# SimCard.net
KiCad netlist of a schematic drawn in Altium Designer
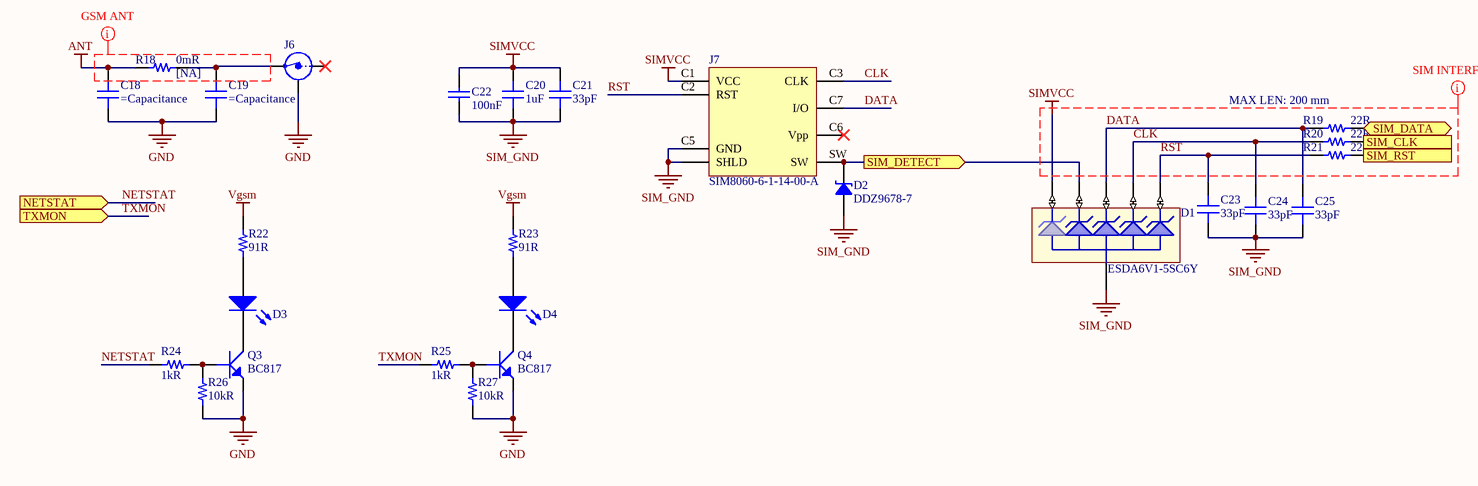
[diagram p0: SimCard.SchDoc]

(export (version "E")
  (design (tool "Eeschema 10.0.6"))
  (components
    (comp (ref "C18")
      (value "~")
      (footprint "CAP 0603/1608")
      (description "Ceramic, SMT Capacitor")
      (libsource (lib "yildizIoT Library") (part "Capacitor - Ceramic"))
    )
    (comp (ref "C19")
      (value "~")
      (footprint "CAP 0603/1608")
      (description "Ceramic, SMT Capacitor")
      (libsource (lib "yildizIoT Library") (part "Capacitor - Ceramic"))
    )
    (comp (ref "C20")
      (value "1uF")
      (footprint "CAP 0603/1608")
      (description "Ceramic, SMT Capacitor")
      (fields
        (field (name "MANUFACTURER") "Samsung")
        (field (name "MANUFACTURER PART NUMBER") "CL10A105KP8NNNC")
      )
      (libsource (lib "yildizIoT Library") (part "Capacitor - Ceramic"))
    )
    (comp (ref "C21")
      (value "33pF")
      (footprint "CAP 0603/1608")
      (description "Ceramic, SMT Capacitor")
      (fields
        (field (name "MANUFACTURER") "Walsin Technologies")
        (field (name "MANUFACTURER PART NUMBER") "0603N330J500CT")
      )
      (libsource (lib "yildizIoT Library") (part "Capacitor - Ceramic"))
    )
    (comp (ref "C22")
      (value "100nF")
      (footprint "CAP 0603/1608")
      (description "Capacitor, Ceramic")
      (fields
        (field (name "MANUFACTURER") "Samsung")
        (field (name "MANUFACTURER PART NUMBER") "CL10A104KA8NNNC")
      )
      (libsource (lib "Muhammet_All_In_One") (part "Cap - Ceramic"))
    )
    (comp (ref "C23")
      (value "33pF")
      (footprint "CAP 0603/1608")
      (description "Ceramic, SMT Capacitor")
      (fields
        (field (name "MANUFACTURER") "Walsin Technologies")
        (field (name "MANUFACTURER PART NUMBER") "0603N330J500CT")
      )
      (libsource (lib "yildizIoT Library") (part "Capacitor - Ceramic"))
    )
    (comp (ref "C24")
      (value "33pF")
      (footprint "CAP 0603/1608")
      (description "Ceramic, SMT Capacitor")
      (fields
        (field (name "MANUFACTURER") "Walsin Technologies")
        (field (name "MANUFACTURER PART NUMBER") "0603N330J500CT")
      )
      (libsource (lib "yildizIoT Library") (part "Capacitor - Ceramic"))
    )
    (comp (ref "C25")
      (value "33pF")
      (footprint "CAP 0603/1608")
      (description "Ceramic, SMT Capacitor")
      (fields
        (field (name "MANUFACTURER") "Walsin Technologies")
        (field (name "MANUFACTURER PART NUMBER") "0603N330J500CT")
      )
      (libsource (lib "yildizIoT Library") (part "Capacitor - Ceramic"))
    )
    (comp (ref "D1")
      (value "ESDA6V1-5SC6Y")
      (footprint "SOT23-6")
      (description "Dual-line Transil™,  transient voltage suppressor (TVS)")
      (fields (field (name "MANUFACTURER") "STMicroelectronics"))
      (libsource (lib "Muhammet_All_In_One") (part "TVS Array 5 ch"))
    )
    (comp (ref "D2")
      (value "DDZ9678-7")
      (footprint "SOD-123")
      (description "DIODE ZENER 1.8V 500MW SOD123")
      (fields (field (name "MANUFACTURER") "Diodes Incorporated") (field (name "TOLERANCE") "±5%"))
      (libsource (lib "Celestial Altium Library - altium_library") (part "Diode Zener"))
    )
    (comp (ref "D3")
      (value "150080VS75000")
      (footprint "LED-0805-A")
      (description "Smd Led")
      (fields (field (name "MANUFACTURER") "Wurth Electronics"))
      (libsource (lib "Muhammet_All_In_One") (part "LED"))
    )
    (comp (ref "D4")
      (value "150080VS75000")
      (footprint "LED-0805-A")
      (description "Smd Led")
      (fields (field (name "MANUFACTURER") "Wurth Electronics"))
      (libsource (lib "Muhammet_All_In_One") (part "LED"))
    )
    (comp (ref "J6")
      (value "1909763-1")
      (footprint "TE C-1909763")
      (description "Coaxial Connector with Switch")
      (fields (field (name "MANUFACTURER") "TE Connectivity AMP"))
      (libsource (lib "yildizIoT Library") (part "RF Connector - UFL"))
    )
    (comp (ref "J7")
      (value "SIM8060-6-1-14-00-A")
      (footprint "GCT SIM8060-6-1-14-00-A")
      (description "CONN SIM NANO HINGED 6P W/SWITCH")
      (fields (field (name "MANUFACTURER") "Global Connector Technology"))
      (libsource (lib "Celestial Altium Library - altium_library") (part "GCT SIM8060-6-1-14-00-A"))
    )
    (comp (ref "Q3")
      (value "BC817")
      (footprint "SOT23-3")
      (description "Transistor, BC817")
      (fields
        (field (name "MANUFACTURER") "ON Semiconductor")
        (field (name "MANUFACTURER PART NUMBER") "BC817-16LT1G")
      )
      (libsource (lib "MuhammetLib") (part "BC817"))
    )
    (comp (ref "Q4")
      (value "BC817")
      (footprint "SOT23-3")
      (description "Transistor, BC817")
      (fields
        (field (name "MANUFACTURER") "ON Semiconductor")
        (field (name "MANUFACTURER PART NUMBER") "BC817-16LT1G")
      )
      (libsource (lib "MuhammetLib") (part "BC817"))
    )
    (comp (ref "R18")
      (value "0mR")
      (footprint "RES 0603/1608")
      (description "Ceramic, SMT Capacitor")
      (fields
        (field (name "MANUFACTURER") "Stackpole Electronics")
        (field (name "MANUFACTURER PART NUMBER") "RMCF0603ZT0R00")
        (field (name "[NA]") "[NA]")
      )
      (libsource (lib "yildizIoT Library") (part "Resistor_Chip"))
    )
    (comp (ref "R19")
      (value "22R")
      (footprint "RES 0603/1608")
      (description "Ceramic, SMT Capacitor")
      (fields
        (field (name "MANUFACTURER") "Yageo")
        (field (name "MANUFACTURER PART NUMBER") "RC0603FR-0722RL")
      )
      (libsource (lib "yildizIoT Library") (part "Resistor_Chip"))
    )
    (comp (ref "R20")
      (value "22R")
      (footprint "RES 0603/1608")
      (description "Ceramic, SMT Capacitor")
      (fields
        (field (name "MANUFACTURER") "Yageo")
        (field (name "MANUFACTURER PART NUMBER") "RC0603FR-0722RL")
      )
      (libsource (lib "yildizIoT Library") (part "Resistor_Chip"))
    )
    (comp (ref "R21")
      (value "22R")
      (footprint "RES 0603/1608")
      (description "Ceramic, SMT Capacitor")
      (fields
        (field (name "MANUFACTURER") "Yageo")
        (field (name "MANUFACTURER PART NUMBER") "RC0603FR-0722RL")
      )
      (libsource (lib "yildizIoT Library") (part "Resistor_Chip"))
    )
    (comp (ref "R22")
      (value "91R")
      (footprint "RES 0603/1608")
      (description "Ceramic, SMT Capacitor")
      (fields
        (field (name "MANUFACTURER") "Yageo")
        (field (name "MANUFACTURER PART NUMBER") "RC0603JR-0791RL")
      )
      (libsource (lib "yildizIoT Library") (part "Resistor_Chip"))
    )
    (comp (ref "R23")
      (value "91R")
      (footprint "RES 0603/1608")
      (description "Ceramic, SMT Capacitor")
      (fields
        (field (name "MANUFACTURER") "Yageo")
        (field (name "MANUFACTURER PART NUMBER") "RC0603JR-0791RL")
      )
      (libsource (lib "yildizIoT Library") (part "Resistor_Chip"))
    )
    (comp (ref "R24")
      (value "1kR")
      (footprint "RES 0603/1608")
      (description "Ceramic, SMT Capacitor")
      (fields (field (name "MANUFACTURER") "Rohm") (field (name "MANUFACTURER PART NUMBER") "ESR03EZPJ102"))
      (libsource (lib "yildizIoT Library") (part "Resistor_Chip"))
    )
    (comp (ref "R25")
      (value "1kR")
      (footprint "RES 0603/1608")
      (description "Ceramic, SMT Capacitor")
      (fields (field (name "MANUFACTURER") "Rohm") (field (name "MANUFACTURER PART NUMBER") "ESR03EZPJ102"))
      (libsource (lib "yildizIoT Library") (part "Resistor_Chip"))
    )
    (comp (ref "R26")
      (value "10kR")
      (footprint "RES 0603/1608")
      (description "Ceramic, SMT Capacitor")
      (fields
        (field (name "MANUFACTURER") "Stackpole Electronics")
        (field (name "MANUFACTURER PART NUMBER") "RNCP0603FTD10K0")
      )
      (libsource (lib "yildizIoT Library") (part "Resistor_Chip"))
    )
    (comp (ref "R27")
      (value "10kR")
      (footprint "RES 0603/1608")
      (description "Ceramic, SMT Capacitor")
      (fields
        (field (name "MANUFACTURER") "Stackpole Electronics")
        (field (name "MANUFACTURER PART NUMBER") "RNCP0603FTD10K0")
      )
      (libsource (lib "yildizIoT Library") (part "Resistor_Chip"))
    )
  )
  (nets
    (net (code "1") (name "/CLK") (class "Default")
      (node (ref "C24") (pin "2") (pinfunction "2_2") (pintype "passive"))
      (node (ref "D1") (pin "5") (pinfunction "5_5") (pintype "bidirectional"))
      (node (ref "J7") (pin "C3") (pinfunction "CLK_C3") (pintype "passive"))
      (node (ref "R20") (pin "1") (pinfunction "1_1") (pintype "passive"))
    )
    (net (code "2") (name "/DATA") (class "Default")
      (node (ref "C25") (pin "2") (pinfunction "2_2") (pintype "passive"))
      (node (ref "D1") (pin "4") (pinfunction "4_4") (pintype "bidirectional"))
      (node (ref "J7") (pin "C7") (pinfunction "I/O_C7") (pintype "passive"))
      (node (ref "R19") (pin "1") (pinfunction "1_1") (pintype "passive"))
    )
    (net (code "3") (name "/NETSTAT") (class "Default")
      (node (ref "R24") (pin "2") (pinfunction "2_2") (pintype "passive"))
    )
    (net (code "4") (name "/RST") (class "Default")
      (node (ref "C23") (pin "2") (pinfunction "2_2") (pintype "passive"))
      (node (ref "D1") (pin "6") (pinfunction "6_6") (pintype "bidirectional"))
      (node (ref "J7") (pin "C2") (pinfunction "RST_C2") (pintype "passive"))
      (node (ref "R21") (pin "1") (pinfunction "1_1") (pintype "passive"))
    )
    (net (code "5") (name "/SIM_CLK") (class "Default")
      (node (ref "R20") (pin "2") (pinfunction "2_2") (pintype "passive"))
    )
    (net (code "6") (name "/SIM_DATA") (class "Default")
      (node (ref "R19") (pin "2") (pinfunction "2_2") (pintype "passive"))
    )
    (net (code "7") (name "/SIM_DETECT") (class "Default")
      (node (ref "D1") (pin "3") (pinfunction "3_3") (pintype "bidirectional"))
      (node (ref "D2") (pin "2") (pinfunction "2_2") (pintype "passive"))
      (node (ref "J7") (pin "SW") (pinfunction "SW_SW") (pintype "passive"))
    )
    (net (code "8") (name "/SIM_RST") (class "Default")
      (node (ref "R21") (pin "2") (pinfunction "2_2") (pintype "passive"))
    )
    (net (code "9") (name "/TXMON") (class "Default")
      (node (ref "R25") (pin "2") (pinfunction "2_2") (pintype "passive"))
    )
    (net (code "10") (name "ANT") (class "Default")
      (node (ref "C18") (pin "2") (pinfunction "2_2") (pintype "passive"))
      (node (ref "R18") (pin "1") (pinfunction "1_1") (pintype "passive"))
    )
    (net (code "11") (name "GND") (class "Default")
      (node (ref "C18") (pin "1") (pinfunction "1_1") (pintype "passive"))
      (node (ref "C19") (pin "1") (pinfunction "1_1") (pintype "passive"))
      (node (ref "J6") (pin "G") (pinfunction "Shield_G") (pintype "passive"))
      (node (ref "Q3") (pin "2") (pinfunction "E_2") (pintype "passive"))
      (node (ref "Q4") (pin "2") (pinfunction "E_2") (pintype "passive"))
      (node (ref "R26") (pin "1") (pinfunction "1_1") (pintype "passive"))
      (node (ref "R27") (pin "1") (pinfunction "1_1") (pintype "passive"))
    )
    (net (code "12") (name "Net-(D3-PadA)") (class "Default")
      (node (ref "D3") (pin "A") (pinfunction "A_A") (pintype "passive"))
      (node (ref "R22") (pin "1") (pinfunction "1_1") (pintype "passive"))
    )
    (net (code "13") (name "Net-(D4-PadA)") (class "Default")
      (node (ref "D4") (pin "A") (pinfunction "A_A") (pintype "passive"))
      (node (ref "R23") (pin "1") (pinfunction "1_1") (pintype "passive"))
    )
    (net (code "14") (name "Net-(J6-OUT)") (class "Default")
      (node (ref "C19") (pin "2") (pinfunction "2_2") (pintype "passive"))
      (node (ref "J6") (pin "S") (pinfunction "OUT_S") (pintype "passive"))
      (node (ref "R18") (pin "2") (pinfunction "2_2") (pintype "passive"))
    )
    (net (code "15") (name "Net-(Q3-B)") (class "Default")
      (node (ref "Q3") (pin "1") (pinfunction "B_1") (pintype "passive"))
      (node (ref "R24") (pin "1") (pinfunction "1_1") (pintype "passive"))
      (node (ref "R26") (pin "2") (pinfunction "2_2") (pintype "passive"))
    )
    (net (code "16") (name "Net-(Q3-C)") (class "Default")
      (node (ref "D3") (pin "K") (pinfunction "K_K") (pintype "passive"))
      (node (ref "Q3") (pin "3") (pinfunction "C_3") (pintype "passive"))
    )
    (net (code "17") (name "Net-(Q4-B)") (class "Default")
      (node (ref "Q4") (pin "1") (pinfunction "B_1") (pintype "passive"))
      (node (ref "R25") (pin "1") (pinfunction "1_1") (pintype "passive"))
      (node (ref "R27") (pin "2") (pinfunction "2_2") (pintype "passive"))
    )
    (net (code "18") (name "Net-(Q4-C)") (class "Default")
      (node (ref "D4") (pin "K") (pinfunction "K_K") (pintype "passive"))
      (node (ref "Q4") (pin "3") (pinfunction "C_3") (pintype "passive"))
    )
    (net (code "19") (name "SIMVCC") (class "Default")
      (node (ref "C20") (pin "2") (pinfunction "2_2") (pintype "passive"))
      (node (ref "C21") (pin "2") (pinfunction "2_2") (pintype "passive"))
      (node (ref "C22") (pin "2") (pinfunction "2_2") (pintype "passive"))
      (node (ref "D1") (pin "1") (pinfunction "1_1") (pintype "bidirectional"))
      (node (ref "J7") (pin "C1") (pinfunction "VCC_C1") (pintype "passive"))
    )
    (net (code "20") (name "SIM_GND") (class "Default")
      (node (ref "C20") (pin "1") (pinfunction "1_1") (pintype "passive"))
      (node (ref "C21") (pin "1") (pinfunction "1_1") (pintype "passive"))
      (node (ref "C22") (pin "1") (pinfunction "1_1") (pintype "passive"))
      (node (ref "C23") (pin "1") (pinfunction "1_1") (pintype "passive"))
      (node (ref "C24") (pin "1") (pinfunction "1_1") (pintype "passive"))
      (node (ref "C25") (pin "1") (pinfunction "1_1") (pintype "passive"))
      (node (ref "D1") (pin "2") (pinfunction "2_2") (pintype "power_in"))
      (node (ref "D2") (pin "1") (pinfunction "1_1") (pintype "passive"))
      (node (ref "J7") (pin "C5") (pinfunction "GND_C5") (pintype "passive"))
      (node (ref "J7") (pin "S") (pinfunction "SHLD_S") (pintype "passive"))
    )
    (net (code "21") (name "Vgsm") (class "Default")
      (node (ref "R22") (pin "2") (pinfunction "2_2") (pintype "passive"))
      (node (ref "R23") (pin "2") (pinfunction "2_2") (pintype "passive"))
    )
    (net (code "22") (name "unconnected-(J6-IN-PadS)") (class "Default")
      (node (ref "J6") (pin "S") (pinfunction "IN_S") (pintype "passive+no_connect"))
    )
    (net (code "23") (name "unconnected-(J7-Vpp-PadC6)") (class "Default")
      (node (ref "J7") (pin "C6") (pinfunction "Vpp_C6") (pintype "passive+no_connect"))
    )
  )
)
